# buffer.net
KiCad netlist of a schematic drawn in EAGLE
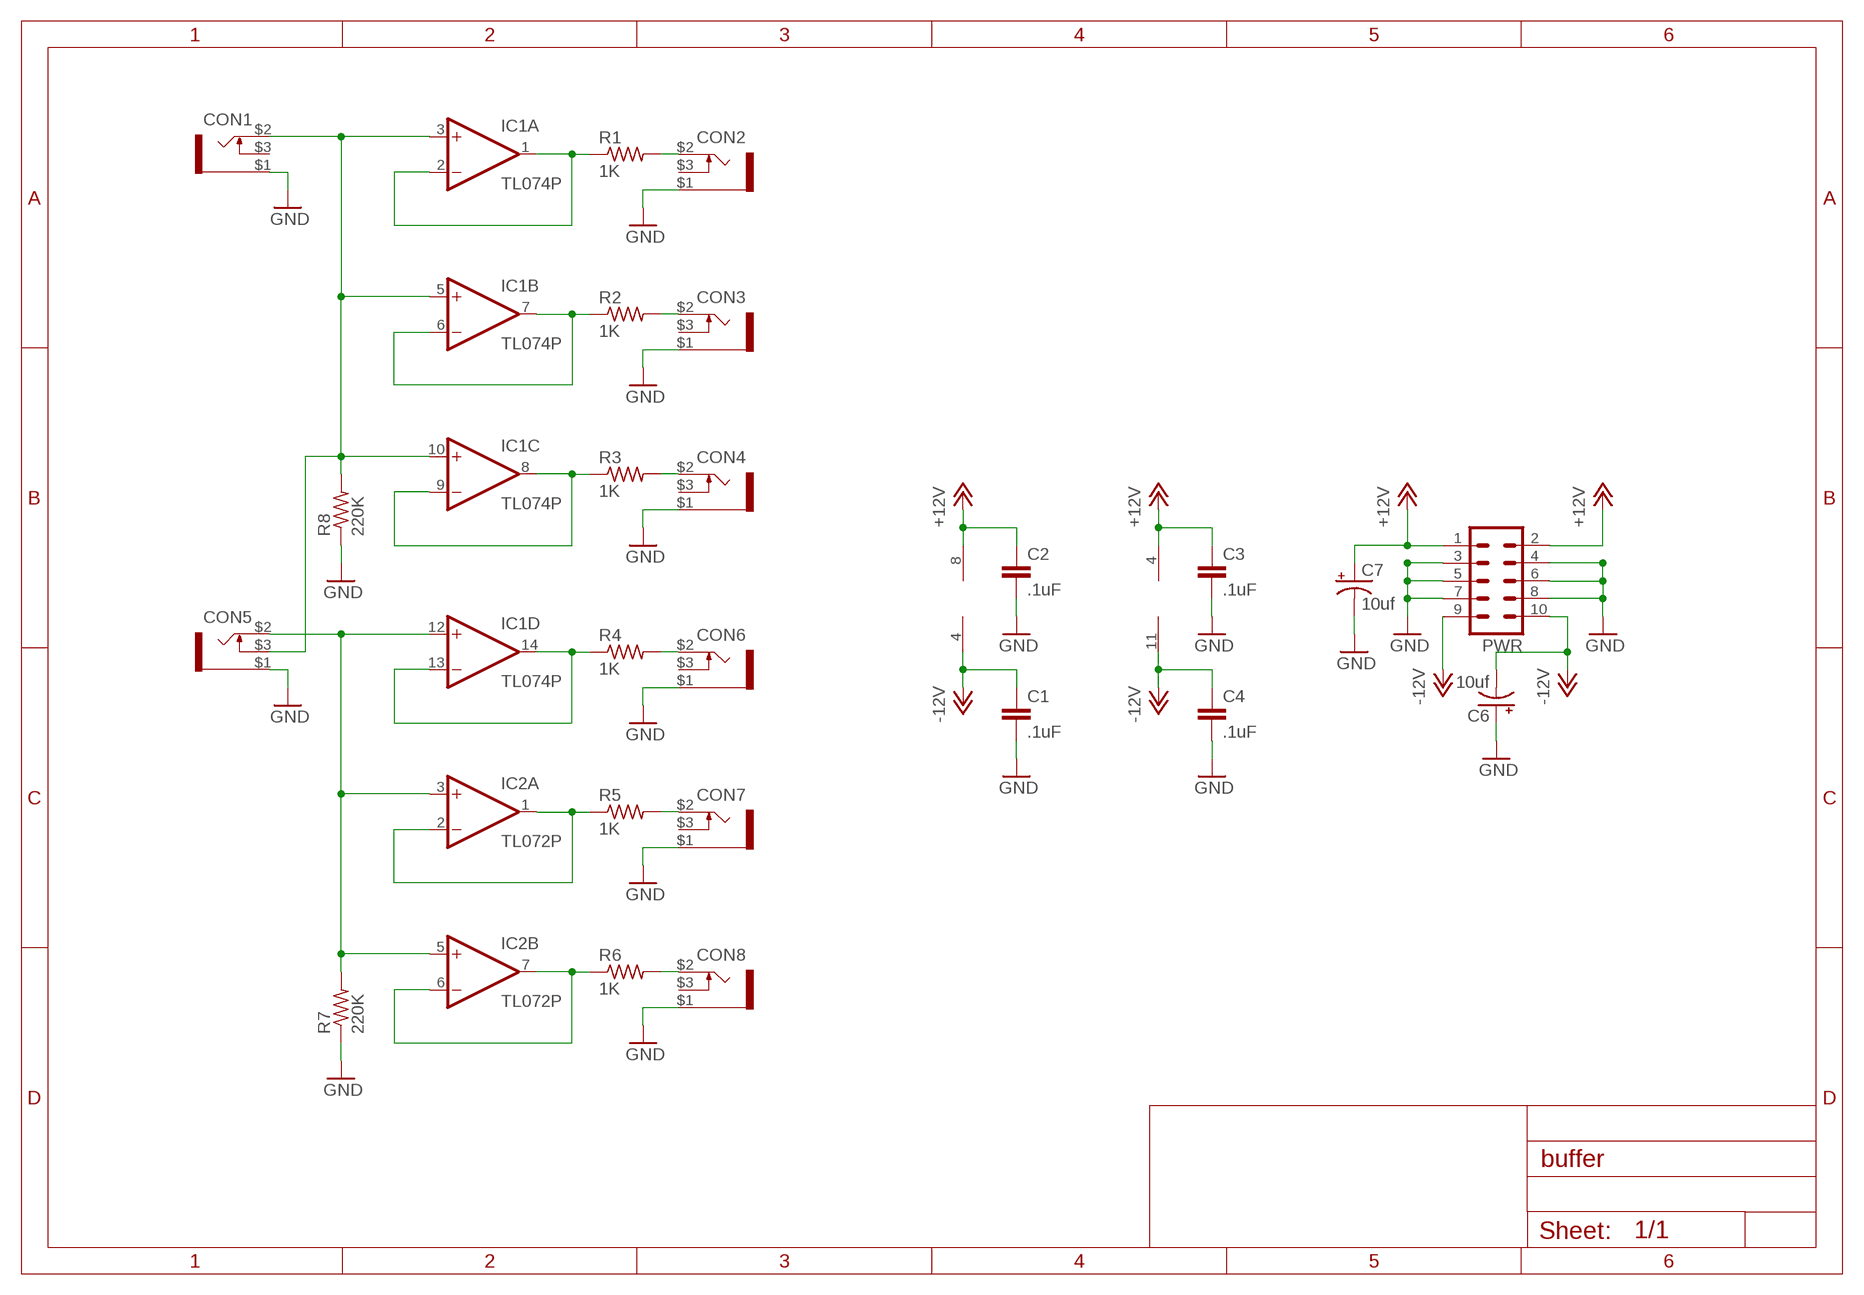
[diagram p0: schematic, sheet 1]

(export (version "E")
  (design (tool "Eeschema 10.0.6"))
  (components
    (comp (ref "C1")
      (value ".1uF")
      (footprint "eagle-import:C050-024X044")
      (libsource (lib "eagle-import") (part "C-EU050-024X044"))
    )
    (comp (ref "C2")
      (value ".1uF")
      (footprint "eagle-import:C050-024X044")
      (libsource (lib "eagle-import") (part "C-EU050-024X044"))
    )
    (comp (ref "C3")
      (value ".1uF")
      (footprint "eagle-import:C050-024X044")
      (libsource (lib "eagle-import") (part "C-EU050-024X044"))
    )
    (comp (ref "C4")
      (value ".1uF")
      (footprint "eagle-import:C050-024X044")
      (libsource (lib "eagle-import") (part "C-EU050-024X044"))
    )
    (comp (ref "C6")
      (value "10uf")
      (footprint "eagle-import:E2,5-5")
      (libsource (lib "eagle-import") (part "CPOL-USE2.5-5"))
    )
    (comp (ref "C7")
      (value "10uf")
      (footprint "eagle-import:E2,5-5")
      (libsource (lib "eagle-import") (part "CPOL-USE2.5-5"))
    )
    (comp (ref "CON1")
      (value "PJ-323PJ-323")
      (footprint "eagle-import:PJ-323")
      (libsource (lib "eagle-import") (part "PJ-323PJ-323"))
    )
    (comp (ref "CON2")
      (value "PJ-323PJ-323")
      (footprint "eagle-import:PJ-323")
      (libsource (lib "eagle-import") (part "PJ-323PJ-323"))
    )
    (comp (ref "CON3")
      (value "PJ-323PJ-323")
      (footprint "eagle-import:PJ-323")
      (libsource (lib "eagle-import") (part "PJ-323PJ-323"))
    )
    (comp (ref "CON4")
      (value "PJ-323PJ-323")
      (footprint "eagle-import:PJ-323")
      (libsource (lib "eagle-import") (part "PJ-323PJ-323"))
    )
    (comp (ref "CON5")
      (value "PJ-323PJ-323")
      (footprint "eagle-import:PJ-323")
      (libsource (lib "eagle-import") (part "PJ-323PJ-323"))
    )
    (comp (ref "CON6")
      (value "PJ-323PJ-323")
      (footprint "eagle-import:PJ-323")
      (libsource (lib "eagle-import") (part "PJ-323PJ-323"))
    )
    (comp (ref "CON7")
      (value "PJ-323PJ-323")
      (footprint "eagle-import:PJ-323")
      (libsource (lib "eagle-import") (part "PJ-323PJ-323"))
    )
    (comp (ref "CON8")
      (value "PJ-323PJ-323")
      (footprint "eagle-import:PJ-323")
      (libsource (lib "eagle-import") (part "PJ-323PJ-323"))
    )
    (comp (ref "IC1")
      (value "TL074P")
      (footprint "eagle-import:DIL14")
      (libsource (lib "eagle-import") (part "TL074P"))
    )
    (comp (ref "IC2")
      (value "TL072P")
      (footprint "eagle-import:DIL08")
      (libsource (lib "eagle-import") (part "TL072P"))
    )
    (comp (ref "PWR")
      (value "ML10")
      (footprint "eagle-import:ML10")
      (libsource (lib "eagle-import") (part "ML10"))
    )
    (comp (ref "R1")
      (value "1K")
      (footprint "eagle-import:0207_2V")
      (libsource (lib "eagle-import") (part "R-US_0207/2V"))
    )
    (comp (ref "R2")
      (value "1K")
      (footprint "eagle-import:0207_2V")
      (libsource (lib "eagle-import") (part "R-US_0207/2V"))
    )
    (comp (ref "R3")
      (value "1K")
      (footprint "eagle-import:0207_2V")
      (libsource (lib "eagle-import") (part "R-US_0207/2V"))
    )
    (comp (ref "R4")
      (value "1K")
      (footprint "eagle-import:0207_2V")
      (libsource (lib "eagle-import") (part "R-US_0207/2V"))
    )
    (comp (ref "R5")
      (value "1K")
      (footprint "eagle-import:0207_2V")
      (libsource (lib "eagle-import") (part "R-US_0207/2V"))
    )
    (comp (ref "R6")
      (value "1K")
      (footprint "eagle-import:0207_2V")
      (libsource (lib "eagle-import") (part "R-US_0207/2V"))
    )
    (comp (ref "R7")
      (value "220K")
      (footprint "eagle-import:0207_2V")
      (libsource (lib "eagle-import") (part "R-US_0207/2V"))
    )
    (comp (ref "R8")
      (value "220K")
      (footprint "eagle-import:0207_2V")
      (libsource (lib "eagle-import") (part "R-US_0207/2V"))
    )
  )
  (nets
    (net (code "1") (name "+12V") (class "Default")
      (node (ref "C2") (pin "1") (pinfunction "1_1") (pintype "passive"))
      (node (ref "C3") (pin "1") (pinfunction "1_1") (pintype "passive"))
      (node (ref "C7") (pin "+") (pinfunction "+_+") (pintype "passive"))
      (node (ref "IC1") (pin "4") (pinfunction "V+_4") (pintype "power_in"))
      (node (ref "IC2") (pin "8") (pinfunction "V+_8") (pintype "power_in"))
      (node (ref "PWR") (pin "1") (pinfunction "1_1") (pintype "passive"))
      (node (ref "PWR") (pin "2") (pinfunction "2_2") (pintype "passive"))
    )
    (net (code "2") (name "-12V") (class "Default")
      (node (ref "C1") (pin "1") (pinfunction "1_1") (pintype "passive"))
      (node (ref "C4") (pin "1") (pinfunction "1_1") (pintype "passive"))
      (node (ref "C6") (pin "-") (pinfunction "-_-") (pintype "passive"))
      (node (ref "IC1") (pin "11") (pinfunction "V-_11") (pintype "power_in"))
      (node (ref "IC2") (pin "4") (pinfunction "V-_4") (pintype "power_in"))
      (node (ref "PWR") (pin "10") (pinfunction "10_10") (pintype "passive"))
      (node (ref "PWR") (pin "9") (pinfunction "9_9") (pintype "passive"))
    )
    (net (code "3") (name "GND") (class "Default")
      (node (ref "C1") (pin "2") (pinfunction "2_2") (pintype "passive"))
      (node (ref "C2") (pin "2") (pinfunction "2_2") (pintype "passive"))
      (node (ref "C3") (pin "2") (pinfunction "2_2") (pintype "passive"))
      (node (ref "C4") (pin "2") (pinfunction "2_2") (pintype "passive"))
      (node (ref "C6") (pin "+") (pinfunction "+_+") (pintype "passive"))
      (node (ref "C7") (pin "-") (pinfunction "-_-") (pintype "passive"))
      (node (ref "CON1") (pin "$1") (pinfunction "3_$1") (pintype "passive"))
      (node (ref "CON2") (pin "$1") (pinfunction "3_$1") (pintype "passive"))
      (node (ref "CON3") (pin "$1") (pinfunction "3_$1") (pintype "passive"))
      (node (ref "CON4") (pin "$1") (pinfunction "3_$1") (pintype "passive"))
      (node (ref "CON5") (pin "$1") (pinfunction "3_$1") (pintype "passive"))
      (node (ref "CON6") (pin "$1") (pinfunction "3_$1") (pintype "passive"))
      (node (ref "CON7") (pin "$1") (pinfunction "3_$1") (pintype "passive"))
      (node (ref "CON8") (pin "$1") (pinfunction "3_$1") (pintype "passive"))
      (node (ref "PWR") (pin "3") (pinfunction "3_3") (pintype "passive"))
      (node (ref "PWR") (pin "4") (pinfunction "4_4") (pintype "passive"))
      (node (ref "PWR") (pin "5") (pinfunction "5_5") (pintype "passive"))
      (node (ref "PWR") (pin "6") (pinfunction "6_6") (pintype "passive"))
      (node (ref "PWR") (pin "7") (pinfunction "7_7") (pintype "passive"))
      (node (ref "PWR") (pin "8") (pinfunction "8_8") (pintype "passive"))
      (node (ref "R7") (pin "1") (pinfunction "1_1") (pintype "passive"))
      (node (ref "R8") (pin "1") (pinfunction "1_1") (pintype "passive"))
    )
    (net (code "4") (name "Net-(CON1-1)") (class "Default")
      (node (ref "CON1") (pin "$2") (pinfunction "1_$2") (pintype "passive"))
      (node (ref "CON5") (pin "$3") (pinfunction "2_$3") (pintype "passive"))
      (node (ref "IC1") (pin "10") (pinfunction "+IN_10") (pintype "input"))
      (node (ref "IC1") (pin "3") (pinfunction "+IN_3") (pintype "input"))
      (node (ref "IC1") (pin "5") (pinfunction "+IN_5") (pintype "input"))
      (node (ref "R8") (pin "2") (pinfunction "2_2") (pintype "passive"))
    )
    (net (code "5") (name "Net-(CON2-1)") (class "Default")
      (node (ref "CON2") (pin "$2") (pinfunction "1_$2") (pintype "passive"))
      (node (ref "R1") (pin "2") (pinfunction "2_2") (pintype "passive"))
    )
    (net (code "6") (name "Net-(CON3-1)") (class "Default")
      (node (ref "CON3") (pin "$2") (pinfunction "1_$2") (pintype "passive"))
      (node (ref "R2") (pin "2") (pinfunction "2_2") (pintype "passive"))
    )
    (net (code "7") (name "Net-(CON4-1)") (class "Default")
      (node (ref "CON4") (pin "$2") (pinfunction "1_$2") (pintype "passive"))
      (node (ref "R3") (pin "2") (pinfunction "2_2") (pintype "passive"))
    )
    (net (code "8") (name "Net-(CON5-1)") (class "Default")
      (node (ref "CON5") (pin "$2") (pinfunction "1_$2") (pintype "passive"))
      (node (ref "IC1") (pin "12") (pinfunction "+IN_12") (pintype "input"))
      (node (ref "IC2") (pin "3") (pinfunction "+IN_3") (pintype "input"))
      (node (ref "IC2") (pin "5") (pinfunction "+IN_5") (pintype "input"))
      (node (ref "R7") (pin "2") (pinfunction "2_2") (pintype "passive"))
    )
    (net (code "9") (name "Net-(CON6-1)") (class "Default")
      (node (ref "CON6") (pin "$2") (pinfunction "1_$2") (pintype "passive"))
      (node (ref "R4") (pin "2") (pinfunction "2_2") (pintype "passive"))
    )
    (net (code "10") (name "Net-(CON7-1)") (class "Default")
      (node (ref "CON7") (pin "$2") (pinfunction "1_$2") (pintype "passive"))
      (node (ref "R5") (pin "2") (pinfunction "2_2") (pintype "passive"))
    )
    (net (code "11") (name "Net-(CON8-1)") (class "Default")
      (node (ref "CON8") (pin "$2") (pinfunction "1_$2") (pintype "passive"))
      (node (ref "R6") (pin "2") (pinfunction "2_2") (pintype "passive"))
    )
    (net (code "12") (name "Net-(IC1A--IN)") (class "Default")
      (node (ref "IC1") (pin "1") (pinfunction "OUT_1") (pintype "output"))
      (node (ref "IC1") (pin "2") (pinfunction "-IN_2") (pintype "input"))
      (node (ref "R1") (pin "1") (pinfunction "1_1") (pintype "passive"))
    )
    (net (code "13") (name "Net-(IC1B--IN)") (class "Default")
      (node (ref "IC1") (pin "6") (pinfunction "-IN_6") (pintype "input"))
      (node (ref "IC1") (pin "7") (pinfunction "OUT_7") (pintype "output"))
      (node (ref "R2") (pin "1") (pinfunction "1_1") (pintype "passive"))
    )
    (net (code "14") (name "Net-(IC1C--IN)") (class "Default")
      (node (ref "IC1") (pin "8") (pinfunction "OUT_8") (pintype "output"))
      (node (ref "IC1") (pin "9") (pinfunction "-IN_9") (pintype "input"))
      (node (ref "R3") (pin "1") (pinfunction "1_1") (pintype "passive"))
    )
    (net (code "15") (name "Net-(IC1D--IN)") (class "Default")
      (node (ref "IC1") (pin "13") (pinfunction "-IN_13") (pintype "input"))
      (node (ref "IC1") (pin "14") (pinfunction "OUT_14") (pintype "output"))
      (node (ref "R4") (pin "1") (pinfunction "1_1") (pintype "passive"))
    )
    (net (code "16") (name "Net-(IC2A--IN)") (class "Default")
      (node (ref "IC2") (pin "1") (pinfunction "OUT_1") (pintype "output"))
      (node (ref "IC2") (pin "2") (pinfunction "-IN_2") (pintype "input"))
      (node (ref "R5") (pin "1") (pinfunction "1_1") (pintype "passive"))
    )
    (net (code "17") (name "Net-(IC2B--IN)") (class "Default")
      (node (ref "IC2") (pin "6") (pinfunction "-IN_6") (pintype "input"))
      (node (ref "IC2") (pin "7") (pinfunction "OUT_7") (pintype "output"))
      (node (ref "R6") (pin "1") (pinfunction "1_1") (pintype "passive"))
    )
    (net (code "18") (name "unconnected-(CON1-2-Pad$3)") (class "Default")
      (node (ref "CON1") (pin "$3") (pinfunction "2_$3") (pintype "passive"))
    )
    (net (code "19") (name "unconnected-(CON2-2-Pad$3)") (class "Default")
      (node (ref "CON2") (pin "$3") (pinfunction "2_$3") (pintype "passive"))
    )
    (net (code "20") (name "unconnected-(CON3-2-Pad$3)") (class "Default")
      (node (ref "CON3") (pin "$3") (pinfunction "2_$3") (pintype "passive"))
    )
    (net (code "21") (name "unconnected-(CON4-2-Pad$3)") (class "Default")
      (node (ref "CON4") (pin "$3") (pinfunction "2_$3") (pintype "passive"))
    )
    (net (code "22") (name "unconnected-(CON6-2-Pad$3)") (class "Default")
      (node (ref "CON6") (pin "$3") (pinfunction "2_$3") (pintype "passive"))
    )
    (net (code "23") (name "unconnected-(CON7-2-Pad$3)") (class "Default")
      (node (ref "CON7") (pin "$3") (pinfunction "2_$3") (pintype "passive"))
    )
    (net (code "24") (name "unconnected-(CON8-2-Pad$3)") (class "Default")
      (node (ref "CON8") (pin "$3") (pinfunction "2_$3") (pintype "passive"))
    )
  )
)
